# Input10-18.net
KiCad netlist of a schematic drawn in Altium Designer
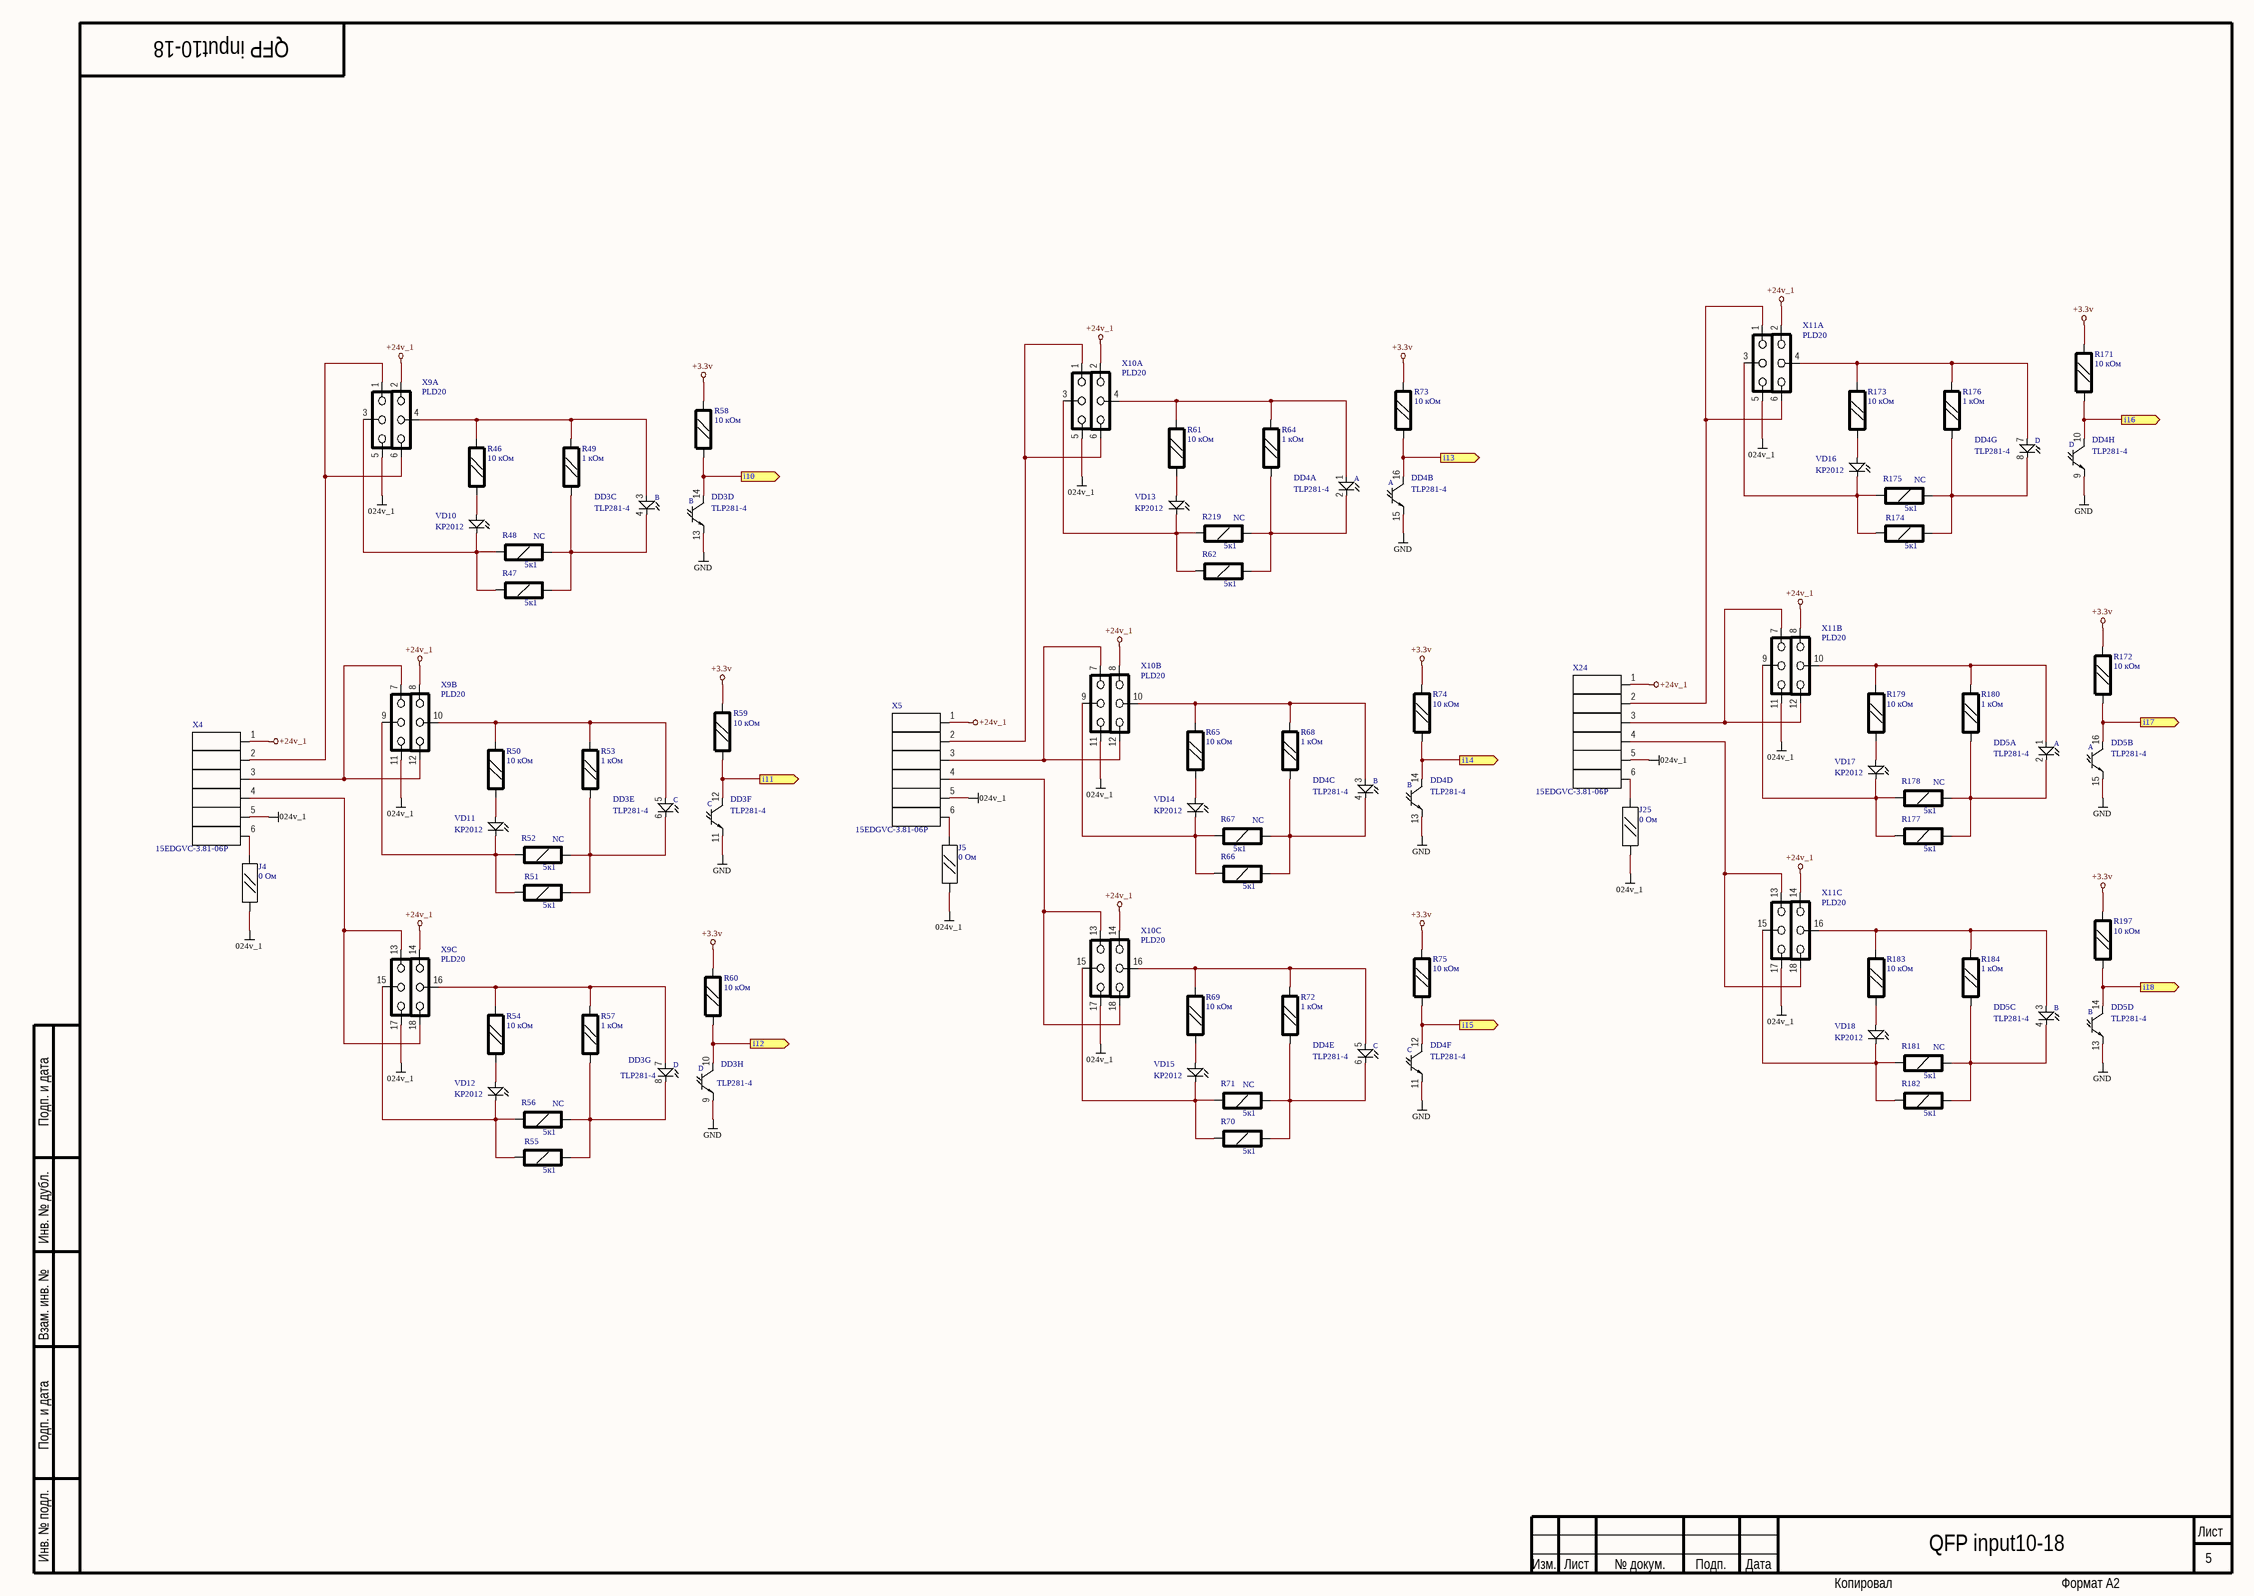
[diagram p0: Input10-18.SchDoc]

(export (version "E")
  (design (tool "Eeschema 10.0.6"))
  (components
    (comp (ref "DD3")
      (value "TLP281-4")
      (footprint "SO16")
      (description "4х канальная транзисторная оптопара")
      (fields (field (name "VOLTAGE") "80V"))
      (libsource (lib "L02_22F") (part "TLP281-4"))
    )
    (comp (ref "DD4")
      (value "TLP281-4")
      (footprint "SO16")
      (description "4х канальная транзисторная оптопара")
      (fields (field (name "VOLTAGE") "80V"))
      (libsource (lib "L02_22F") (part "TLP281-4"))
    )
    (comp (ref "DD5")
      (value "TLP281-4")
      (footprint "SO16")
      (description "4х канальная транзисторная оптопара")
      (fields (field (name "VOLTAGE") "80V"))
      (libsource (lib "L02_22F") (part "TLP281-4"))
    )
    (comp (ref "J4")
      (value "0 Ом")
      (footprint "SMD0805RES")
      (description "SMD 0805 перемычка")
      (libsource (lib "iL03_22") (part "JR0805"))
    )
    (comp (ref "J5")
      (value "0 Ом")
      (footprint "SMD0805RES")
      (description "SMD 0805 перемычка")
      (libsource (lib "iL03_22") (part "JR0805"))
    )
    (comp (ref "J25")
      (value "0 Ом")
      (footprint "SMD0805RES")
      (description "SMD 0805 перемычка")
      (libsource (lib "iL03_22") (part "JR0805"))
    )
    (comp (ref "R46")
      (value "10 кОм")
      (footprint "SMD0805RES")
      (description "Чип резистор 0805")
      (fields (field (name "TOLERANCE") "5%"))
      (libsource (lib "SL02_22F") (part "R0805"))
    )
    (comp (ref "R47")
      (value "5к1")
      (footprint "RES1206")
      (description "Чип резистор 1206")
      (fields (field (name "TOLERANCE") "5%"))
      (libsource (lib "SL02_22F") (part "R1206"))
    )
    (comp (ref "R48")
      (value "5к1")
      (footprint "RES1206")
      (description "Чип резистор 1206")
      (fields (field (name "TOLERANCE") "5%") (field (name "SOLDEROPTON") "NC"))
      (libsource (lib "SL02_22F") (part "R1206"))
    )
    (comp (ref "R49")
      (value "1 кОм")
      (footprint "SMD0805RES")
      (description "Чип резистор 0805")
      (fields (field (name "TOLERANCE") "5%"))
      (libsource (lib "SL02_22F") (part "R0805"))
    )
    (comp (ref "R50")
      (value "10 кОм")
      (footprint "SMD0805RES")
      (description "Чип резистор 0805")
      (fields (field (name "TOLERANCE") "5%"))
      (libsource (lib "SL02_22F") (part "R0805"))
    )
    (comp (ref "R51")
      (value "5к1")
      (footprint "RES1206")
      (description "Чип резистор 1206")
      (fields (field (name "TOLERANCE") "5%"))
      (libsource (lib "SL02_22F") (part "R1206"))
    )
    (comp (ref "R52")
      (value "5к1")
      (footprint "RES1206")
      (description "Чип резистор 1206")
      (fields (field (name "TOLERANCE") "5%") (field (name "SOLDEROPTON") "NC"))
      (libsource (lib "SL02_22F") (part "R1206"))
    )
    (comp (ref "R53")
      (value "1 кОм")
      (footprint "SMD0805RES")
      (description "Чип резистор 0805")
      (fields (field (name "TOLERANCE") "5%"))
      (libsource (lib "SL02_22F") (part "R0805"))
    )
    (comp (ref "R54")
      (value "10 кОм")
      (footprint "SMD0805RES")
      (description "Чип резистор 0805")
      (fields (field (name "TOLERANCE") "5%"))
      (libsource (lib "SL02_22F") (part "R0805"))
    )
    (comp (ref "R55")
      (value "5к1")
      (footprint "RES1206")
      (description "Чип резистор 1206")
      (fields (field (name "TOLERANCE") "5%"))
      (libsource (lib "SL02_22F") (part "R1206"))
    )
    (comp (ref "R56")
      (value "5к1")
      (footprint "RES1206")
      (description "Чип резистор 1206")
      (fields (field (name "TOLERANCE") "5%") (field (name "SOLDEROPTON") "NC"))
      (libsource (lib "SL02_22F") (part "R1206"))
    )
    (comp (ref "R57")
      (value "1 кОм")
      (footprint "SMD0805RES")
      (description "Чип резистор 0805")
      (fields (field (name "TOLERANCE") "5%"))
      (libsource (lib "SL02_22F") (part "R0805"))
    )
    (comp (ref "R58")
      (value "10 кОм")
      (footprint "SMD0805RES")
      (description "Чип резистор 0805")
      (fields (field (name "TOLERANCE") "5%"))
      (libsource (lib "SL02_22F") (part "R0805"))
    )
    (comp (ref "R59")
      (value "10 кОм")
      (footprint "SMD0805RES")
      (description "Чип резистор 0805")
      (fields (field (name "TOLERANCE") "5%"))
      (libsource (lib "SL02_22F") (part "R0805"))
    )
    (comp (ref "R60")
      (value "10 кОм")
      (footprint "SMD0805RES")
      (description "Чип резистор 0805")
      (fields (field (name "TOLERANCE") "5%"))
      (libsource (lib "SL02_22F") (part "R0805"))
    )
    (comp (ref "R61")
      (value "10 кОм")
      (footprint "SMD0805RES")
      (description "Чип резистор 0805")
      (fields (field (name "TOLERANCE") "5%"))
      (libsource (lib "SL02_22F") (part "R0805"))
    )
    (comp (ref "R62")
      (value "5к1")
      (footprint "RES1206")
      (description "Чип резистор 1206")
      (fields (field (name "TOLERANCE") "5%"))
      (libsource (lib "SL02_22F") (part "R1206"))
    )
    (comp (ref "R64")
      (value "1 кОм")
      (footprint "SMD0805RES")
      (description "Чип резистор 0805")
      (fields (field (name "TOLERANCE") "5%"))
      (libsource (lib "SL02_22F") (part "R0805"))
    )
    (comp (ref "R65")
      (value "10 кОм")
      (footprint "SMD0805RES")
      (description "Чип резистор 0805")
      (fields (field (name "TOLERANCE") "5%"))
      (libsource (lib "SL02_22F") (part "R0805"))
    )
    (comp (ref "R66")
      (value "5к1")
      (footprint "RES1206")
      (description "Чип резистор 1206")
      (fields (field (name "TOLERANCE") "5%"))
      (libsource (lib "SL02_22F") (part "R1206"))
    )
    (comp (ref "R67")
      (value "5к1")
      (footprint "RES1206")
      (description "Чип резистор 1206")
      (fields (field (name "TOLERANCE") "5%") (field (name "SOLDEROPTON") "NC"))
      (libsource (lib "SL02_22F") (part "R1206"))
    )
    (comp (ref "R68")
      (value "1 кОм")
      (footprint "SMD0805RES")
      (description "Чип резистор 0805")
      (fields (field (name "TOLERANCE") "5%"))
      (libsource (lib "SL02_22F") (part "R0805"))
    )
    (comp (ref "R69")
      (value "10 кОм")
      (footprint "SMD0805RES")
      (description "Чип резистор 0805")
      (fields (field (name "TOLERANCE") "5%"))
      (libsource (lib "SL02_22F") (part "R0805"))
    )
    (comp (ref "R70")
      (value "5к1")
      (footprint "RES1206")
      (description "Чип резистор 1206")
      (fields (field (name "TOLERANCE") "5%"))
      (libsource (lib "SL02_22F") (part "R1206"))
    )
    (comp (ref "R71")
      (value "5к1")
      (footprint "RES1206")
      (description "Чип резистор 1206")
      (fields (field (name "TOLERANCE") "5%") (field (name "SOLDEROPTON") "NC"))
      (libsource (lib "SL02_22F") (part "R1206"))
    )
    (comp (ref "R72")
      (value "1 кОм")
      (footprint "SMD0805RES")
      (description "Чип резистор 0805")
      (fields (field (name "TOLERANCE") "5%"))
      (libsource (lib "SL02_22F") (part "R0805"))
    )
    (comp (ref "R73")
      (value "10 кОм")
      (footprint "SMD0805RES")
      (description "Чип резистор 0805")
      (fields (field (name "TOLERANCE") "5%"))
      (libsource (lib "SL02_22F") (part "R0805"))
    )
    (comp (ref "R74")
      (value "10 кОм")
      (footprint "SMD0805RES")
      (description "Чип резистор 0805")
      (fields (field (name "TOLERANCE") "5%"))
      (libsource (lib "SL02_22F") (part "R0805"))
    )
    (comp (ref "R75")
      (value "10 кОм")
      (footprint "SMD0805RES")
      (description "Чип резистор 0805")
      (fields (field (name "TOLERANCE") "5%"))
      (libsource (lib "SL02_22F") (part "R0805"))
    )
    (comp (ref "R171")
      (value "10 кОм")
      (footprint "SMD0805RES")
      (description "Чип резистор 0805")
      (fields (field (name "TOLERANCE") "5%"))
      (libsource (lib "SL02_22F") (part "R0805"))
    )
    (comp (ref "R172")
      (value "10 кОм")
      (footprint "SMD0805RES")
      (description "Чип резистор 0805")
      (fields (field (name "TOLERANCE") "5%"))
      (libsource (lib "SL02_22F") (part "R0805"))
    )
    (comp (ref "R173")
      (value "10 кОм")
      (footprint "SMD0805RES")
      (description "Чип резистор 0805")
      (fields (field (name "TOLERANCE") "5%"))
      (libsource (lib "SL02_22F") (part "R0805"))
    )
    (comp (ref "R174")
      (value "5к1")
      (footprint "RES1206")
      (description "Чип резистор 1206")
      (fields (field (name "TOLERANCE") "5%"))
      (libsource (lib "SL02_22F") (part "R1206"))
    )
    (comp (ref "R175")
      (value "5к1")
      (footprint "RES1206")
      (description "Чип резистор 1206")
      (fields (field (name "TOLERANCE") "5%") (field (name "SOLDEROPTON") "NC"))
      (libsource (lib "SL02_22F") (part "R1206"))
    )
    (comp (ref "R176")
      (value "1 кОм")
      (footprint "SMD0805RES")
      (description "Чип резистор 0805")
      (fields (field (name "TOLERANCE") "5%"))
      (libsource (lib "SL02_22F") (part "R0805"))
    )
    (comp (ref "R177")
      (value "5к1")
      (footprint "RES1206")
      (description "Чип резистор 1206")
      (fields (field (name "TOLERANCE") "5%"))
      (libsource (lib "SL02_22F") (part "R1206"))
    )
    (comp (ref "R178")
      (value "5к1")
      (footprint "RES1206")
      (description "Чип резистор 1206")
      (fields (field (name "TOLERANCE") "5%") (field (name "SOLDEROPTON") "NC"))
      (libsource (lib "SL02_22F") (part "R1206"))
    )
    (comp (ref "R179")
      (value "10 кОм")
      (footprint "SMD0805RES")
      (description "Чип резистор 0805")
      (fields (field (name "TOLERANCE") "5%"))
      (libsource (lib "SL02_22F") (part "R0805"))
    )
    (comp (ref "R180")
      (value "1 кОм")
      (footprint "SMD0805RES")
      (description "Чип резистор 0805")
      (fields (field (name "TOLERANCE") "5%"))
      (libsource (lib "SL02_22F") (part "R0805"))
    )
    (comp (ref "R181")
      (value "5к1")
      (footprint "RES1206")
      (description "Чип резистор 1206")
      (fields (field (name "TOLERANCE") "5%") (field (name "SOLDEROPTON") "NC"))
      (libsource (lib "SL02_22F") (part "R1206"))
    )
    (comp (ref "R182")
      (value "5к1")
      (footprint "RES1206")
      (description "Чип резистор 1206")
      (fields (field (name "TOLERANCE") "5%"))
      (libsource (lib "SL02_22F") (part "R1206"))
    )
    (comp (ref "R183")
      (value "10 кОм")
      (footprint "SMD0805RES")
      (description "Чип резистор 0805")
      (fields (field (name "TOLERANCE") "5%"))
      (libsource (lib "SL02_22F") (part "R0805"))
    )
    (comp (ref "R184")
      (value "1 кОм")
      (footprint "SMD0805RES")
      (description "Чип резистор 0805")
      (fields (field (name "TOLERANCE") "5%"))
      (libsource (lib "SL02_22F") (part "R0805"))
    )
    (comp (ref "R197")
      (value "10 кОм")
      (footprint "SMD0805RES")
      (description "Чип резистор 0805")
      (fields (field (name "TOLERANCE") "5%"))
      (libsource (lib "SL02_22F") (part "R0805"))
    )
    (comp (ref "R219")
      (value "5к1")
      (footprint "RES1206")
      (description "Чип резистор 1206")
      (fields (field (name "TOLERANCE") "5%") (field (name "SOLDEROPTON") "NC"))
      (libsource (lib "SL02_22F") (part "R1206"))
    )
    (comp (ref "VD10")
      (value "KP2012")
      (footprint "SMD0805DIO_C")
      (description "Чип светодиод 0805")
      (libsource (lib "L02_22F") (part "KP2012_C"))
    )
    (comp (ref "VD11")
      (value "KP2012")
      (footprint "SMD0805DIO_C")
      (description "Чип светодиод 0805")
      (libsource (lib "L02_22F") (part "KP2012_C"))
    )
    (comp (ref "VD12")
      (value "KP2012")
      (footprint "SMD0805DIO_C")
      (description "Чип светодиод 0805")
      (libsource (lib "L02_22F") (part "KP2012_C"))
    )
    (comp (ref "VD13")
      (value "KP2012")
      (footprint "SMD0805DIO_C")
      (description "Чип светодиод 0805")
      (libsource (lib "L02_22F") (part "KP2012_C"))
    )
    (comp (ref "VD14")
      (value "KP2012")
      (footprint "SMD0805DIO_C")
      (description "Чип светодиод 0805")
      (libsource (lib "L02_22F") (part "KP2012_C"))
    )
    (comp (ref "VD15")
      (value "KP2012")
      (footprint "SMD0805DIO_C")
      (description "Чип светодиод 0805")
      (libsource (lib "L02_22F") (part "KP2012_C"))
    )
    (comp (ref "VD16")
      (value "KP2012")
      (footprint "SMD0805DIO_C")
      (description "Чип светодиод 0805")
      (libsource (lib "L02_22F") (part "KP2012_C"))
    )
    (comp (ref "VD17")
      (value "KP2012")
      (footprint "SMD0805DIO_C")
      (description "Чип светодиод 0805")
      (libsource (lib "L02_22F") (part "KP2012_C"))
    )
    (comp (ref "VD18")
      (value "KP2012")
      (footprint "SMD0805DIO_C")
      (description "Чип светодиод 0805")
      (libsource (lib "L02_22F") (part "KP2012_C"))
    )
    (comp (ref "X4")
      (value "15EDGVC-3.81-06P")
      (footprint "15EDGVC_081_6")
      (description "Вилка  6/3.81")
      (fields (field (name "VOLTAGE") "2кВ"))
      (libsource (lib "L02_22F") (part "15EDGVC-3.81-06P"))
    )
    (comp (ref "X5")
      (value "15EDGVC-3.81-06P")
      (footprint "15EDGVC_081_6")
      (description "Вилка  6/3.81")
      (fields (field (name "VOLTAGE") "2кВ"))
      (libsource (lib "L02_22F") (part "15EDGVC-3.81-06P"))
    )
    (comp (ref "X9")
      (value "PLD20")
      (footprint "pld2x10_1.27")
      (description "Вилка  PLD 20/1.27")
      (libsource (lib "SL02_22F") (part "PLD20"))
    )
    (comp (ref "X10")
      (value "PLD20")
      (footprint "pld2x10_1.27")
      (description "Вилка  PLD 20/1.27")
      (libsource (lib "SL02_22F") (part "PLD20"))
    )
    (comp (ref "X11")
      (value "PLD20")
      (footprint "pld2x10_1.27")
      (description "Вилка  PLD 20/1.27")
      (libsource (lib "SL02_22F") (part "PLD20"))
    )
    (comp (ref "X24")
      (value "15EDGVC-3.81-06P")
      (footprint "15EDGVC_081_6")
      (description "Вилка  6/3.81")
      (fields (field (name "VOLTAGE") "2кВ"))
      (libsource (lib "L02_22F") (part "15EDGVC-3.81-06P"))
    )
  )
  (nets
    (net (code "1") (name "+3.3v") (class "Default")
      (node (ref "R171") (pin "2") (pinfunction "2_2") (pintype "passive"))
      (node (ref "R172") (pin "2") (pinfunction "2_2") (pintype "passive"))
      (node (ref "R197") (pin "2") (pinfunction "2_2") (pintype "passive"))
      (node (ref "R58") (pin "2") (pinfunction "2_2") (pintype "passive"))
      (node (ref "R59") (pin "2") (pinfunction "2_2") (pintype "passive"))
      (node (ref "R60") (pin "2") (pinfunction "2_2") (pintype "passive"))
      (node (ref "R73") (pin "2") (pinfunction "2_2") (pintype "passive"))
      (node (ref "R74") (pin "2") (pinfunction "2_2") (pintype "passive"))
      (node (ref "R75") (pin "2") (pinfunction "2_2") (pintype "passive"))
    )
    (net (code "2") (name "+24v_1") (class "Default")
      (node (ref "X10") (pin "14") (pinfunction "14_14") (pintype "passive"))
      (node (ref "X10") (pin "2") (pinfunction "2_2") (pintype "passive"))
      (node (ref "X10") (pin "8") (pinfunction "8_8") (pintype "passive"))
      (node (ref "X11") (pin "14") (pinfunction "14_14") (pintype "passive"))
      (node (ref "X11") (pin "2") (pinfunction "2_2") (pintype "passive"))
      (node (ref "X11") (pin "8") (pinfunction "8_8") (pintype "passive"))
      (node (ref "X24") (pin "1") (pinfunction "1_1") (pintype "passive"))
      (node (ref "X4") (pin "1") (pinfunction "1_1") (pintype "passive"))
      (node (ref "X5") (pin "1") (pinfunction "1_1") (pintype "passive"))
      (node (ref "X9") (pin "14") (pinfunction "14_14") (pintype "passive"))
      (node (ref "X9") (pin "2") (pinfunction "2_2") (pintype "passive"))
      (node (ref "X9") (pin "8") (pinfunction "8_8") (pintype "passive"))
    )
    (net (code "3") (name "/i10") (class "Default")
      (node (ref "DD3") (pin "14") (pinfunction "Collector_B_14") (pintype "passive"))
      (node (ref "R58") (pin "1") (pinfunction "1_1") (pintype "passive"))
    )
    (net (code "4") (name "/i11") (class "Default")
      (node (ref "DD3") (pin "12") (pinfunction "Collector_C_12") (pintype "passive"))
      (node (ref "R59") (pin "1") (pinfunction "1_1") (pintype "passive"))
    )
    (net (code "5") (name "/i12") (class "Default")
      (node (ref "DD3") (pin "10") (pinfunction "Collector_D_10") (pintype "passive"))
      (node (ref "R60") (pin "1") (pinfunction "1_1") (pintype "passive"))
    )
    (net (code "6") (name "/i13") (class "Default")
      (node (ref "DD4") (pin "16") (pinfunction "Collector_A_16") (pintype "passive"))
      (node (ref "R73") (pin "1") (pinfunction "1_1") (pintype "passive"))
    )
    (net (code "7") (name "/i14") (class "Default")
      (node (ref "DD4") (pin "14") (pinfunction "Collector_B_14") (pintype "passive"))
      (node (ref "R74") (pin "1") (pinfunction "1_1") (pintype "passive"))
    )
    (net (code "8") (name "/i15") (class "Default")
      (node (ref "DD4") (pin "12") (pinfunction "Collector_C_12") (pintype "passive"))
      (node (ref "R75") (pin "1") (pinfunction "1_1") (pintype "passive"))
    )
    (net (code "9") (name "/i16") (class "Default")
      (node (ref "DD4") (pin "10") (pinfunction "Collector_D_10") (pintype "passive"))
      (node (ref "R171") (pin "1") (pinfunction "1_1") (pintype "passive"))
    )
    (net (code "10") (name "/i17") (class "Default")
      (node (ref "DD5") (pin "16") (pinfunction "Collector_A_16") (pintype "passive"))
      (node (ref "R172") (pin "1") (pinfunction "1_1") (pintype "passive"))
    )
    (net (code "11") (name "/i18") (class "Default")
      (node (ref "DD5") (pin "14") (pinfunction "Collector_B_14") (pintype "passive"))
      (node (ref "R197") (pin "1") (pinfunction "1_1") (pintype "passive"))
    )
    (net (code "12") (name "024v_1") (class "Default")
      (node (ref "J25") (pin "2") (pinfunction "2_2") (pintype "passive"))
      (node (ref "J4") (pin "2") (pinfunction "2_2") (pintype "passive"))
      (node (ref "J5") (pin "2") (pinfunction "2_2") (pintype "passive"))
      (node (ref "X10") (pin "11") (pinfunction "11_11") (pintype "passive"))
      (node (ref "X10") (pin "17") (pinfunction "17_17") (pintype "passive"))
      (node (ref "X10") (pin "5") (pinfunction "5_5") (pintype "passive"))
      (node (ref "X11") (pin "11") (pinfunction "11_11") (pintype "passive"))
      (node (ref "X11") (pin "17") (pinfunction "17_17") (pintype "passive"))
      (node (ref "X11") (pin "5") (pinfunction "5_5") (pintype "passive"))
      (node (ref "X24") (pin "5") (pinfunction "5_5") (pintype "passive"))
      (node (ref "X4") (pin "5") (pinfunction "5_5") (pintype "passive"))
      (node (ref "X5") (pin "5") (pinfunction "5_5") (pintype "passive"))
      (node (ref "X9") (pin "11") (pinfunction "11_11") (pintype "passive"))
      (node (ref "X9") (pin "17") (pinfunction "17_17") (pintype "passive"))
      (node (ref "X9") (pin "5") (pinfunction "5_5") (pintype "passive"))
    )
    (net (code "13") (name "GND") (class "Default")
      (node (ref "DD3") (pin "11") (pinfunction "Emitter_C_11") (pintype "passive"))
      (node (ref "DD3") (pin "13") (pinfunction "Emitter_B_13") (pintype "passive"))
      (node (ref "DD3") (pin "9") (pinfunction "Emitter_D_9") (pintype "passive"))
      (node (ref "DD4") (pin "11") (pinfunction "Emitter_C_11") (pintype "passive"))
      (node (ref "DD4") (pin "13") (pinfunction "Emitter_B_13") (pintype "passive"))
      (node (ref "DD4") (pin "15") (pinfunction "Emitter_A_15") (pintype "passive"))
      (node (ref "DD4") (pin "9") (pinfunction "Emitter_D_9") (pintype "passive"))
      (node (ref "DD5") (pin "13") (pinfunction "Emitter_B_13") (pintype "passive"))
      (node (ref "DD5") (pin "15") (pinfunction "Emitter_A_15") (pintype "passive"))
    )
    (net (code "14") (name "Net-(DD3C-Anode_B)") (class "Default")
      (node (ref "DD3") (pin "3") (pinfunction "Anode_B_3") (pintype "passive"))
      (node (ref "R46") (pin "1") (pinfunction "1_1") (pintype "passive"))
      (node (ref "R49") (pin "1") (pinfunction "1_1") (pintype "passive"))
      (node (ref "X9") (pin "4") (pinfunction "4_4") (pintype "passive"))
    )
    (net (code "15") (name "Net-(DD3C-Cathode_B)") (class "Default")
      (node (ref "DD3") (pin "4") (pinfunction "Cathode_B_4") (pintype "passive"))
      (node (ref "R47") (pin "2") (pinfunction "2_2") (pintype "passive"))
      (node (ref "R48") (pin "2") (pinfunction "2_2") (pintype "passive"))
      (node (ref "R49") (pin "2") (pinfunction "2_2") (pintype "passive"))
    )
    (net (code "16") (name "Net-(DD3E-Anode_C)") (class "Default")
      (node (ref "DD3") (pin "5") (pinfunction "Anode_C_5") (pintype "passive"))
      (node (ref "R50") (pin "1") (pinfunction "1_1") (pintype "passive"))
      (node (ref "R53") (pin "1") (pinfunction "1_1") (pintype "passive"))
      (node (ref "X9") (pin "10") (pinfunction "10_10") (pintype "passive"))
    )
    (net (code "17") (name "Net-(DD3E-Cathode)") (class "Default")
      (node (ref "DD3") (pin "6") (pinfunction "Cathode_6") (pintype "passive"))
      (node (ref "R51") (pin "2") (pinfunction "2_2") (pintype "passive"))
      (node (ref "R52") (pin "2") (pinfunction "2_2") (pintype "passive"))
      (node (ref "R53") (pin "2") (pinfunction "2_2") (pintype "passive"))
    )
    (net (code "18") (name "Net-(DD3G-Anode_D)") (class "Default")
      (node (ref "DD3") (pin "7") (pinfunction "Anode_D_7") (pintype "passive"))
      (node (ref "R54") (pin "1") (pinfunction "1_1") (pintype "passive"))
      (node (ref "R57") (pin "1") (pinfunction "1_1") (pintype "passive"))
      (node (ref "X9") (pin "16") (pinfunction "16_16") (pintype "passive"))
    )
    (net (code "19") (name "Net-(DD3G-Cathode_D)") (class "Default")
      (node (ref "DD3") (pin "8") (pinfunction "Cathode_D_8") (pintype "passive"))
      (node (ref "R55") (pin "2") (pinfunction "2_2") (pintype "passive"))
      (node (ref "R56") (pin "2") (pinfunction "2_2") (pintype "passive"))
      (node (ref "R57") (pin "2") (pinfunction "2_2") (pintype "passive"))
    )
    (net (code "20") (name "Net-(DD4A-Anode_A)") (class "Default")
      (node (ref "DD4") (pin "1") (pinfunction "Anode_A_1") (pintype "passive"))
      (node (ref "R61") (pin "1") (pinfunction "1_1") (pintype "passive"))
      (node (ref "R64") (pin "1") (pinfunction "1_1") (pintype "passive"))
      (node (ref "X10") (pin "4") (pinfunction "4_4") (pintype "passive"))
    )
    (net (code "21") (name "Net-(DD4A-Cathode_A)") (class "Default")
      (node (ref "DD4") (pin "2") (pinfunction "Cathode_A_2") (pintype "passive"))
      (node (ref "R219") (pin "2") (pinfunction "2_2") (pintype "passive"))
      (node (ref "R62") (pin "2") (pinfunction "2_2") (pintype "passive"))
      (node (ref "R64") (pin "2") (pinfunction "2_2") (pintype "passive"))
    )
    (net (code "22") (name "Net-(DD4C-Anode_B)") (class "Default")
      (node (ref "DD4") (pin "3") (pinfunction "Anode_B_3") (pintype "passive"))
      (node (ref "R65") (pin "1") (pinfunction "1_1") (pintype "passive"))
      (node (ref "R68") (pin "1") (pinfunction "1_1") (pintype "passive"))
      (node (ref "X10") (pin "10") (pinfunction "10_10") (pintype "passive"))
    )
    (net (code "23") (name "Net-(DD4C-Cathode_B)") (class "Default")
      (node (ref "DD4") (pin "4") (pinfunction "Cathode_B_4") (pintype "passive"))
      (node (ref "R66") (pin "2") (pinfunction "2_2") (pintype "passive"))
      (node (ref "R67") (pin "2") (pinfunction "2_2") (pintype "passive"))
      (node (ref "R68") (pin "2") (pinfunction "2_2") (pintype "passive"))
    )
    (net (code "24") (name "Net-(DD4E-Anode_C)") (class "Default")
      (node (ref "DD4") (pin "5") (pinfunction "Anode_C_5") (pintype "passive"))
      (node (ref "R69") (pin "1") (pinfunction "1_1") (pintype "passive"))
      (node (ref "R72") (pin "1") (pinfunction "1_1") (pintype "passive"))
      (node (ref "X10") (pin "16") (pinfunction "16_16") (pintype "passive"))
    )
    (net (code "25") (name "Net-(DD4E-Cathode)") (class "Default")
      (node (ref "DD4") (pin "6") (pinfunction "Cathode_6") (pintype "passive"))
      (node (ref "R70") (pin "2") (pinfunction "2_2") (pintype "passive"))
      (node (ref "R71") (pin "2") (pinfunction "2_2") (pintype "passive"))
      (node (ref "R72") (pin "2") (pinfunction "2_2") (pintype "passive"))
    )
    (net (code "26") (name "Net-(DD4G-Anode_D)") (class "Default")
      (node (ref "DD4") (pin "7") (pinfunction "Anode_D_7") (pintype "passive"))
      (node (ref "R173") (pin "1") (pinfunction "1_1") (pintype "passive"))
      (node (ref "R176") (pin "1") (pinfunction "1_1") (pintype "passive"))
      (node (ref "X11") (pin "4") (pinfunction "4_4") (pintype "passive"))
    )
    (net (code "27") (name "Net-(DD4G-Cathode_D)") (class "Default")
      (node (ref "DD4") (pin "8") (pinfunction "Cathode_D_8") (pintype "passive"))
      (node (ref "R174") (pin "2") (pinfunction "2_2") (pintype "passive"))
      (node (ref "R175") (pin "2") (pinfunction "2_2") (pintype "passive"))
      (node (ref "R176") (pin "2") (pinfunction "2_2") (pintype "passive"))
    )
    (net (code "28") (name "Net-(DD5A-Anode_A)") (class "Default")
      (node (ref "DD5") (pin "1") (pinfunction "Anode_A_1") (pintype "passive"))
      (node (ref "R179") (pin "1") (pinfunction "1_1") (pintype "passive"))
      (node (ref "R180") (pin "1") (pinfunction "1_1") (pintype "passive"))
      (node (ref "X11") (pin "10") (pinfunction "10_10") (pintype "passive"))
    )
    (net (code "29") (name "Net-(DD5A-Cathode_A)") (class "Default")
      (node (ref "DD5") (pin "2") (pinfunction "Cathode_A_2") (pintype "passive"))
      (node (ref "R177") (pin "2") (pinfunction "2_2") (pintype "passive"))
      (node (ref "R178") (pin "2") (pinfunction "2_2") (pintype "passive"))
      (node (ref "R180") (pin "2") (pinfunction "2_2") (pintype "passive"))
    )
    (net (code "30") (name "Net-(DD5C-Anode_B)") (class "Default")
      (node (ref "DD5") (pin "3") (pinfunction "Anode_B_3") (pintype "passive"))
      (node (ref "R183") (pin "1") (pinfunction "1_1") (pintype "passive"))
      (node (ref "R184") (pin "1") (pinfunction "1_1") (pintype "passive"))
      (node (ref "X11") (pin "16") (pinfunction "16_16") (pintype "passive"))
    )
    (net (code "31") (name "Net-(DD5C-Cathode_B)") (class "Default")
      (node (ref "DD5") (pin "4") (pinfunction "Cathode_B_4") (pintype "passive"))
      (node (ref "R181") (pin "2") (pinfunction "2_2") (pintype "passive"))
      (node (ref "R182") (pin "2") (pinfunction "2_2") (pintype "passive"))
      (node (ref "R184") (pin "2") (pinfunction "2_2") (pintype "passive"))
    )
    (net (code "32") (name "Net-(J4-Pad1)") (class "Default")
      (node (ref "J4") (pin "1") (pinfunction "1_1") (pintype "passive"))
      (node (ref "X4") (pin "6") (pinfunction "6_6") (pintype "passive"))
    )
    (net (code "33") (name "Net-(J5-Pad1)") (class "Default")
      (node (ref "J5") (pin "1") (pinfunction "1_1") (pintype "passive"))
      (node (ref "X5") (pin "6") (pinfunction "6_6") (pintype "passive"))
    )
    (net (code "34") (name "Net-(J25-Pad1)") (class "Default")
      (node (ref "J25") (pin "1") (pinfunction "1_1") (pintype "passive"))
      (node (ref "X24") (pin "6") (pinfunction "6_6") (pintype "passive"))
    )
    (net (code "35") (name "Net-(VD10-Anode)") (class "Default")
      (node (ref "R46") (pin "2") (pinfunction "2_2") (pintype "passive"))
      (node (ref "VD10") (pin "2") (pinfunction "Anode_2") (pintype "passive"))
    )
    (net (code "36") (name "Net-(VD10-Cathode)") (class "Default")
      (node (ref "R47") (pin "1") (pinfunction "1_1") (pintype "passive"))
      (node (ref "R48") (pin "1") (pinfunction "1_1") (pintype "passive"))
      (node (ref "VD10") (pin "1") (pinfunction "Cathode_1") (pintype "passive"))
      (node (ref "X9") (pin "3") (pinfunction "3_3") (pintype "passive"))
    )
    (net (code "37") (name "Net-(VD11-Anode)") (class "Default")
      (node (ref "R50") (pin "2") (pinfunction "2_2") (pintype "passive"))
      (node (ref "VD11") (pin "2") (pinfunction "Anode_2") (pintype "passive"))
    )
    (net (code "38") (name "Net-(VD11-Cathode)") (class "Default")
      (node (ref "R51") (pin "1") (pinfunction "1_1") (pintype "passive"))
      (node (ref "R52") (pin "1") (pinfunction "1_1") (pintype "passive"))
      (node (ref "VD11") (pin "1") (pinfunction "Cathode_1") (pintype "passive"))
      (node (ref "X9") (pin "9") (pinfunction "9_9") (pintype "passive"))
    )
    (net (code "39") (name "Net-(VD12-Anode)") (class "Default")
      (node (ref "R54") (pin "2") (pinfunction "2_2") (pintype "passive"))
      (node (ref "VD12") (pin "2") (pinfunction "Anode_2") (pintype "passive"))
    )
    (net (code "40") (name "Net-(VD12-Cathode)") (class "Default")
      (node (ref "R55") (pin "1") (pinfunction "1_1") (pintype "passive"))
      (node (ref "R56") (pin "1") (pinfunction "1_1") (pintype "passive"))
      (node (ref "VD12") (pin "1") (pinfunction "Cathode_1") (pintype "passive"))
      (node (ref "X9") (pin "15") (pinfunction "15_15") (pintype "passive"))
    )
    (net (code "41") (name "Net-(VD13-Anode)") (class "Default")
      (node (ref "R61") (pin "2") (pinfunction "2_2") (pintype "passive"))
      (node (ref "VD13") (pin "2") (pinfunction "Anode_2") (pintype "passive"))
    )
    (net (code "42") (name "Net-(VD13-Cathode)") (class "Default")
      (node (ref "R219") (pin "1") (pinfunction "1_1") (pintype "passive"))
      (node (ref "R62") (pin "1") (pinfunction "1_1") (pintype "passive"))
      (node (ref "VD13") (pin "1") (pinfunction "Cathode_1") (pintype "passive"))
      (node (ref "X10") (pin "3") (pinfunction "3_3") (pintype "passive"))
    )
    (net (code "43") (name "Net-(VD14-Anode)") (class "Default")
      (node (ref "R65") (pin "2") (pinfunction "2_2") (pintype "passive"))
      (node (ref "VD14") (pin "2") (pinfunction "Anode_2") (pintype "passive"))
    )
    (net (code "44") (name "Net-(VD14-Cathode)") (class "Default")
      (node (ref "R66") (pin "1") (pinfunction "1_1") (pintype "passive"))
      (node (ref "R67") (pin "1") (pinfunction "1_1") (pintype "passive"))
      (node (ref "VD14") (pin "1") (pinfunction "Cathode_1") (pintype "passive"))
      (node (ref "X10") (pin "9") (pinfunction "9_9") (pintype "passive"))
    )
    (net (code "45") (name "Net-(VD15-Anode)") (class "Default")
      (node (ref "R69") (pin "2") (pinfunction "2_2") (pintype "passive"))
      (node (ref "VD15") (pin "2") (pinfunction "Anode_2") (pintype "passive"))
    )
    (net (code "46") (name "Net-(VD15-Cathode)") (class "Default")
      (node (ref "R70") (pin "1") (pinfunction "1_1") (pintype "passive"))
      (node (ref "R71") (pin "1") (pinfunction "1_1") (pintype "passive"))
      (node (ref "VD15") (pin "1") (pinfunction "Cathode_1") (pintype "passive"))
      (node (ref "X10") (pin "15") (pinfunction "15_15") (pintype "passive"))
    )
    (net (code "47") (name "Net-(VD16-Anode)") (class "Default")
      (node (ref "R173") (pin "2") (pinfunction "2_2") (pintype "passive"))
      (node (ref "VD16") (pin "2") (pinfunction "Anode_2") (pintype "passive"))
    )
    (net (code "48") (name "Net-(VD16-Cathode)") (class "Default")
      (node (ref "R174") (pin "1") (pinfunction "1_1") (pintype "passive"))
      (node (ref "R175") (pin "1") (pinfunction "1_1") (pintype "passive"))
      (node (ref "VD16") (pin "1") (pinfunction "Cathode_1") (pintype "passive"))
      (node (ref "X11") (pin "3") (pinfunction "3_3") (pintype "passive"))
    )
    (net (code "49") (name "Net-(VD17-Anode)") (class "Default")
      (node (ref "R179") (pin "2") (pinfunction "2_2") (pintype "passive"))
      (node (ref "VD17") (pin "2") (pinfunction "Anode_2") (pintype "passive"))
    )
    (net (code "50") (name "Net-(VD17-Cathode)") (class "Default")
      (node (ref "R177") (pin "1") (pinfunction "1_1") (pintype "passive"))
      (node (ref "R178") (pin "1") (pinfunction "1_1") (pintype "passive"))
      (node (ref "VD17") (pin "1") (pinfunction "Cathode_1") (pintype "passive"))
      (node (ref "X11") (pin "9") (pinfunction "9_9") (pintype "passive"))
    )
    (net (code "51") (name "Net-(VD18-Anode)") (class "Default")
      (node (ref "R183") (pin "2") (pinfunction "2_2") (pintype "passive"))
      (node (ref "VD18") (pin "2") (pinfunction "Anode_2") (pintype "passive"))
    )
    (net (code "52") (name "Net-(VD18-Cathode)") (class "Default")
      (node (ref "R181") (pin "1") (pinfunction "1_1") (pintype "passive"))
      (node (ref "R182") (pin "1") (pinfunction "1_1") (pintype "passive"))
      (node (ref "VD18") (pin "1") (pinfunction "Cathode_1") (pintype "passive"))
      (node (ref "X11") (pin "15") (pinfunction "15_15") (pintype "passive"))
    )
    (net (code "53") (name "Net-(X4-Pad2)") (class "Default")
      (node (ref "X4") (pin "2") (pinfunction "2_2") (pintype "passive"))
      (node (ref "X9") (pin "1") (pinfunction "1_1") (pintype "passive"))
      (node (ref "X9") (pin "6") (pinfunction "6_6") (pintype "passive"))
    )
    (net (code "54") (name "Net-(X4-Pad3)") (class "Default")
      (node (ref "X4") (pin "3") (pinfunction "3_3") (pintype "passive"))
      (node (ref "X9") (pin "12") (pinfunction "12_12") (pintype "passive"))
      (node (ref "X9") (pin "7") (pinfunction "7_7") (pintype "passive"))
    )
    (net (code "55") (name "Net-(X4-Pad4)") (class "Default")
      (node (ref "X4") (pin "4") (pinfunction "4_4") (pintype "passive"))
      (node (ref "X9") (pin "13") (pinfunction "13_13") (pintype "passive"))
      (node (ref "X9") (pin "18") (pinfunction "18_18") (pintype "passive"))
    )
    (net (code "56") (name "Net-(X10-Pad1)") (class "Default")
      (node (ref "X10") (pin "1") (pinfunction "1_1") (pintype "passive"))
      (node (ref "X10") (pin "6") (pinfunction "6_6") (pintype "passive"))
      (node (ref "X5") (pin "2") (pinfunction "2_2") (pintype "passive"))
    )
    (net (code "57") (name "Net-(X10-Pad12)") (class "Default")
      (node (ref "X10") (pin "12") (pinfunction "12_12") (pintype "passive"))
      (node (ref "X10") (pin "7") (pinfunction "7_7") (pintype "passive"))
      (node (ref "X5") (pin "3") (pinfunction "3_3") (pintype "passive"))
    )
    (net (code "58") (name "Net-(X10-Pad13)") (class "Default")
      (node (ref "X10") (pin "13") (pinfunction "13_13") (pintype "passive"))
      (node (ref "X10") (pin "18") (pinfunction "18_18") (pintype "passive"))
      (node (ref "X5") (pin "4") (pinfunction "4_4") (pintype "passive"))
    )
    (net (code "59") (name "Net-(X11-Pad1)") (class "Default")
      (node (ref "X11") (pin "1") (pinfunction "1_1") (pintype "passive"))
      (node (ref "X11") (pin "6") (pinfunction "6_6") (pintype "passive"))
      (node (ref "X24") (pin "2") (pinfunction "2_2") (pintype "passive"))
    )
    (net (code "60") (name "Net-(X11-Pad12)") (class "Default")
      (node (ref "X11") (pin "12") (pinfunction "12_12") (pintype "passive"))
      (node (ref "X11") (pin "7") (pinfunction "7_7") (pintype "passive"))
      (node (ref "X24") (pin "3") (pinfunction "3_3") (pintype "passive"))
    )
    (net (code "61") (name "Net-(X11-Pad13)") (class "Default")
      (node (ref "X11") (pin "13") (pinfunction "13_13") (pintype "passive"))
      (node (ref "X11") (pin "18") (pinfunction "18_18") (pintype "passive"))
      (node (ref "X24") (pin "4") (pinfunction "4_4") (pintype "passive"))
    )
  )
)
